# Qwiic_Shield_for_Teensy.net
KiCad netlist of a schematic drawn in EAGLE
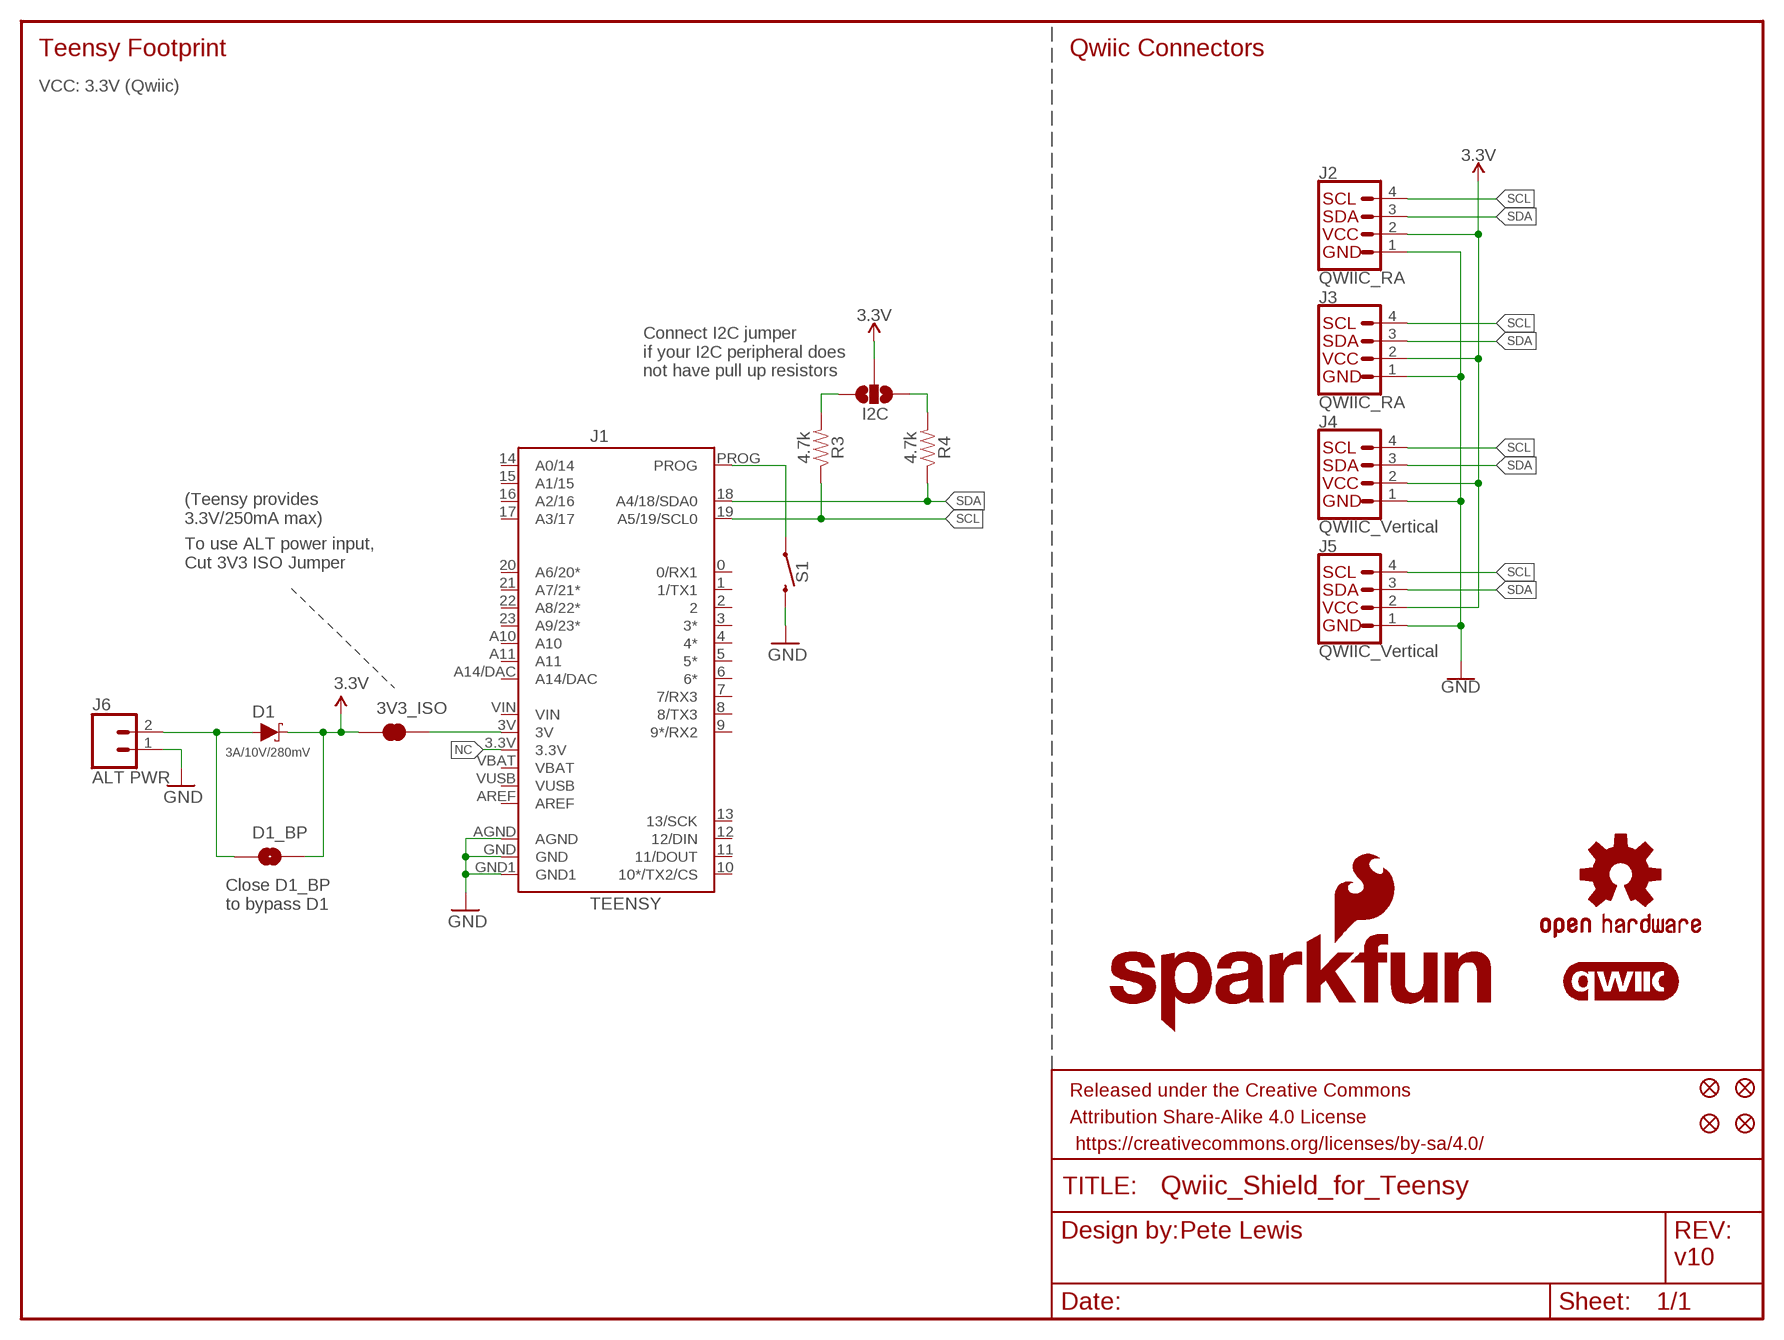
[diagram p0: schematic, sheet 1]

(export (version "E")
  (design (tool "Eeschema 10.0.6"))
  (components
    (comp (ref "3V3_ISO")
      (value "JUMPER-SMT_2_NC_TRACE_SILK")
      (footprint "eagle-import:SMT-JUMPER_2_NC_TRACE_SILK")
      (libsource (lib "eagle-import") (part "JUMPER-SMT_2_NC_TRACE_SILK"))
    )
    (comp (ref "D1")
      (value "3A/10V/280mV")
      (footprint "eagle-import:SOD-323")
      (libsource (lib "eagle-import") (part "DIODE-SCHOTTKY-BAT60A"))
    )
    (comp (ref "D1_BP")
      (value "JUMPER-SMT_2_NO_SILK")
      (footprint "eagle-import:SMT-JUMPER_2_NO_SILK")
      (libsource (lib "eagle-import") (part "JUMPER-SMT_2_NO_SILK"))
    )
    (comp (ref "FD1")
      (value "FIDUCIAL1X2")
      (footprint "eagle-import:FIDUCIAL-1X2")
      (libsource (lib "eagle-import") (part "FIDUCIAL1X2"))
    )
    (comp (ref "FD2")
      (value "FIDUCIAL1X2")
      (footprint "eagle-import:FIDUCIAL-1X2")
      (libsource (lib "eagle-import") (part "FIDUCIAL1X2"))
    )
    (comp (ref "FD3")
      (value "FIDUCIAL1X2")
      (footprint "eagle-import:FIDUCIAL-1X2")
      (libsource (lib "eagle-import") (part "FIDUCIAL1X2"))
    )
    (comp (ref "FD4")
      (value "FIDUCIAL1X2")
      (footprint "eagle-import:FIDUCIAL-1X2")
      (libsource (lib "eagle-import") (part "FIDUCIAL1X2"))
    )
    (comp (ref "FRAME1")
      (value "FRAME-LETTER")
      (footprint "eagle-import:CREATIVE_COMMONS")
      (libsource (lib "eagle-import") (part "FRAME-LETTER"))
    )
    (comp (ref "I2C")
      (value "JUMPER-SMT_3_NO_SILK")
      (footprint "eagle-import:SMT-JUMPER_3_NO_SILK")
      (libsource (lib "eagle-import") (part "JUMPER-SMT_3_NO_SILK"))
    )
    (comp (ref "J1")
      (value "TEENSY")
      (footprint "eagle-import:TEENSY_NOSILK")
      (libsource (lib "eagle-import") (part "TEENSYNOSILK"))
    )
    (comp (ref "J2")
      (value "QWIIC_RA")
      (footprint "eagle-import:JST04_1MM_RA")
      (libsource (lib "eagle-import") (part "QWIIC_CONNECTORJS-1MM"))
    )
    (comp (ref "J3")
      (value "QWIIC_RA")
      (footprint "eagle-import:JST04_1MM_RA")
      (libsource (lib "eagle-import") (part "QWIIC_CONNECTORJS-1MM"))
    )
    (comp (ref "J4")
      (value "QWIIC_Vertical")
      (footprint "eagle-import:JST04_1MM_VERT")
      (libsource (lib "eagle-import") (part "QWIIC_CONNECTOR"))
    )
    (comp (ref "J5")
      (value "QWIIC_Vertical")
      (footprint "eagle-import:JST04_1MM_VERT")
      (libsource (lib "eagle-import") (part "QWIIC_CONNECTOR"))
    )
    (comp (ref "J6")
      (value "ALT PWR")
      (footprint "eagle-import:1X02_NO_SILK")
      (libsource (lib "eagle-import") (part "CONN_021X02_NO_SILK"))
    )
    (comp (ref "LOGO1")
      (value "SFE_LOGO_NAME_FLAME.1_INCH")
      (footprint "eagle-import:SFE_LOGO_NAME_FLAME_.1")
      (libsource (lib "eagle-import") (part "SFE_LOGO_NAME_FLAME.1_INCH"))
    )
    (comp (ref "LOGO2")
      (value "SFE_LOGO_FLAME.1_INCH")
      (footprint "eagle-import:SFE_LOGO_FLAME_.1")
      (libsource (lib "eagle-import") (part "SFE_LOGO_FLAME.1_INCH"))
    )
    (comp (ref "LOGO3")
      (value "OSHW-LOGOS")
      (footprint "eagle-import:OSHW-LOGO-S")
      (libsource (lib "eagle-import") (part "OSHW-LOGOS"))
    )
    (comp (ref "LOGO4")
      (value "QWIIC_LOGO_5MM")
      (footprint "eagle-import:QWIIC_5MM")
      (libsource (lib "eagle-import") (part "QWIIC_LOGO_5MM"))
    )
    (comp (ref "R3")
      (value "4.7k")
      (footprint "eagle-import:0603")
      (libsource (lib "eagle-import") (part "4.7KOHM-0603-1/10W-1%"))
    )
    (comp (ref "R4")
      (value "4.7k")
      (footprint "eagle-import:0603")
      (libsource (lib "eagle-import") (part "4.7KOHM-0603-1/10W-1%"))
    )
    (comp (ref "S1")
      (value "SMD_5.2MM")
      (footprint "eagle-import:TACTILE_SWITCH_SMD_5.2MM")
      (libsource (lib "eagle-import") (part "MOMENTARY-SWITCH-SPST-SMD-5.2MM-TALL"))
    )
  )
  (nets
    (net (code "1") (name "/VBAT") (class "Default")
      (node (ref "J1") (pin "VBAT") (pinfunction "VBAT_VBAT") (pintype "power_in"))
    )
    (net (code "2") (name "/VIN") (class "Default")
      (node (ref "J1") (pin "VIN") (pinfunction "VIN_VIN") (pintype "power_in"))
    )
    (net (code "3") (name "/VUSB") (class "Default")
      (node (ref "J1") (pin "VUSB") (pinfunction "VUSB_VUSB") (pintype "power_in"))
    )
    (net (code "4") (name "3.3V") (class "Default")
      (node (ref "3V3_ISO") (pin "1") (pinfunction "1_1") (pintype "passive"))
      (node (ref "D1") (pin "C") (pinfunction "C_C") (pintype "passive"))
      (node (ref "D1_BP") (pin "2") (pinfunction "2_2") (pintype "passive"))
      (node (ref "I2C") (pin "2") (pinfunction "2_2") (pintype "passive"))
      (node (ref "J2") (pin "2") (pinfunction "2_2") (pintype "power_in"))
      (node (ref "J3") (pin "2") (pinfunction "2_2") (pintype "power_in"))
      (node (ref "J4") (pin "2") (pinfunction "2_2") (pintype "power_in"))
      (node (ref "J5") (pin "2") (pinfunction "2_2") (pintype "power_in"))
    )
    (net (code "5") (name "GND") (class "Default")
      (node (ref "J1") (pin "AGND") (pinfunction "AGND_AGND") (pintype "power_in"))
      (node (ref "J1") (pin "GND") (pinfunction "GND_GND") (pintype "power_in"))
      (node (ref "J1") (pin "GND1") (pinfunction "GND1_GND1") (pintype "power_in"))
      (node (ref "J2") (pin "1") (pinfunction "1_1") (pintype "power_in"))
      (node (ref "J3") (pin "1") (pinfunction "1_1") (pintype "power_in"))
      (node (ref "J4") (pin "1") (pinfunction "1_1") (pintype "power_in"))
      (node (ref "J5") (pin "1") (pinfunction "1_1") (pintype "power_in"))
      (node (ref "J6") (pin "1") (pinfunction "1_1") (pintype "passive"))
      (node (ref "S1") (pin "3") (pinfunction "2_3") (pintype "passive"))
    )
    (net (code "6") (name "NC") (class "Default")
      (node (ref "J1") (pin "3.3V") (pinfunction "3.3V_3.3V") (pintype "power_in"))
    )
    (net (code "7") (name "Net-(3V3_ISO-Pad2)") (class "Default")
      (node (ref "3V3_ISO") (pin "2") (pinfunction "2_2") (pintype "passive"))
      (node (ref "J1") (pin "3V") (pinfunction "3V_3V") (pintype "power_in"))
    )
    (net (code "8") (name "Net-(D1-PadA)") (class "Default")
      (node (ref "D1") (pin "A") (pinfunction "A_A") (pintype "passive"))
      (node (ref "D1_BP") (pin "1") (pinfunction "1_1") (pintype "passive"))
      (node (ref "J6") (pin "2") (pinfunction "2_2") (pintype "passive"))
    )
    (net (code "9") (name "Net-(I2C-Pad1)") (class "Default")
      (node (ref "I2C") (pin "1") (pinfunction "1_1") (pintype "passive"))
      (node (ref "R3") (pin "2") (pinfunction "2_2") (pintype "passive"))
    )
    (net (code "10") (name "Net-(I2C-Pad3)") (class "Default")
      (node (ref "I2C") (pin "3") (pinfunction "3_3") (pintype "passive"))
      (node (ref "R4") (pin "2") (pinfunction "2_2") (pintype "passive"))
    )
    (net (code "11") (name "Net-(J1-PadPROG)") (class "Default")
      (node (ref "J1") (pin "PROG") (pinfunction "PROG_PROG") (pintype "bidirectional"))
      (node (ref "S1") (pin "1") (pinfunction "1_1") (pintype "passive"))
    )
    (net (code "12") (name "SCL") (class "Default")
      (node (ref "J1") (pin "19") (pinfunction "A5/19/SCL0_19") (pintype "bidirectional"))
      (node (ref "J2") (pin "4") (pinfunction "4_4") (pintype "passive"))
      (node (ref "J3") (pin "4") (pinfunction "4_4") (pintype "passive"))
      (node (ref "J4") (pin "4") (pinfunction "4_4") (pintype "passive"))
      (node (ref "J5") (pin "4") (pinfunction "4_4") (pintype "passive"))
      (node (ref "R3") (pin "1") (pinfunction "1_1") (pintype "passive"))
    )
    (net (code "13") (name "SDA") (class "Default")
      (node (ref "J1") (pin "18") (pinfunction "A4/18/SDA0_18") (pintype "bidirectional"))
      (node (ref "J2") (pin "3") (pinfunction "3_3") (pintype "passive"))
      (node (ref "J3") (pin "3") (pinfunction "3_3") (pintype "passive"))
      (node (ref "J4") (pin "3") (pinfunction "3_3") (pintype "passive"))
      (node (ref "J5") (pin "3") (pinfunction "3_3") (pintype "passive"))
      (node (ref "R4") (pin "1") (pinfunction "1_1") (pintype "passive"))
    )
    (net (code "14") (name "unconnected-(J1-0{slash}RX1-Pad0)") (class "Default")
      (node (ref "J1") (pin "0") (pinfunction "0/RX1_0") (pintype "bidirectional"))
    )
    (net (code "15") (name "unconnected-(J1-1{slash}TX1-Pad1)") (class "Default")
      (node (ref "J1") (pin "1") (pinfunction "1/TX1_1") (pintype "bidirectional"))
    )
    (net (code "16") (name "unconnected-(J1-3*-Pad3)") (class "Default")
      (node (ref "J1") (pin "3") (pinfunction "3*_3") (pintype "bidirectional"))
    )
    (net (code "17") (name "unconnected-(J1-4*-Pad4)") (class "Default")
      (node (ref "J1") (pin "4") (pinfunction "4*_4") (pintype "bidirectional"))
    )
    (net (code "18") (name "unconnected-(J1-5*-Pad5)") (class "Default")
      (node (ref "J1") (pin "5") (pinfunction "5*_5") (pintype "bidirectional"))
    )
    (net (code "19") (name "unconnected-(J1-6*-Pad6)") (class "Default")
      (node (ref "J1") (pin "6") (pinfunction "6*_6") (pintype "bidirectional"))
    )
    (net (code "20") (name "unconnected-(J1-7{slash}RX3-Pad7)") (class "Default")
      (node (ref "J1") (pin "7") (pinfunction "7/RX3_7") (pintype "bidirectional"))
    )
    (net (code "21") (name "unconnected-(J1-8{slash}TX3-Pad8)") (class "Default")
      (node (ref "J1") (pin "8") (pinfunction "8/TX3_8") (pintype "bidirectional"))
    )
    (net (code "22") (name "unconnected-(J1-9*{slash}RX2-Pad9)") (class "Default")
      (node (ref "J1") (pin "9") (pinfunction "9*/RX2_9") (pintype "bidirectional"))
    )
    (net (code "23") (name "unconnected-(J1-10*{slash}TX2{slash}CS-Pad10)") (class "Default")
      (node (ref "J1") (pin "10") (pinfunction "10*/TX2/CS_10") (pintype "bidirectional"))
    )
    (net (code "24") (name "unconnected-(J1-11{slash}DOUT-Pad11)") (class "Default")
      (node (ref "J1") (pin "11") (pinfunction "11/DOUT_11") (pintype "bidirectional"))
    )
    (net (code "25") (name "unconnected-(J1-12{slash}DIN-Pad12)") (class "Default")
      (node (ref "J1") (pin "12") (pinfunction "12/DIN_12") (pintype "bidirectional"))
    )
    (net (code "26") (name "unconnected-(J1-13{slash}SCK-Pad13)") (class "Default")
      (node (ref "J1") (pin "13") (pinfunction "13/SCK_13") (pintype "bidirectional"))
    )
    (net (code "27") (name "unconnected-(J1-A0{slash}14-Pad14)") (class "Default")
      (node (ref "J1") (pin "14") (pinfunction "A0/14_14") (pintype "bidirectional"))
    )
    (net (code "28") (name "unconnected-(J1-A1{slash}15-Pad15)") (class "Default")
      (node (ref "J1") (pin "15") (pinfunction "A1/15_15") (pintype "bidirectional"))
    )
    (net (code "29") (name "unconnected-(J1-A2{slash}16-Pad16)") (class "Default")
      (node (ref "J1") (pin "16") (pinfunction "A2/16_16") (pintype "bidirectional"))
    )
    (net (code "30") (name "unconnected-(J1-A3{slash}17-Pad17)") (class "Default")
      (node (ref "J1") (pin "17") (pinfunction "A3/17_17") (pintype "bidirectional"))
    )
    (net (code "31") (name "unconnected-(J1-A6{slash}20*-Pad20)") (class "Default")
      (node (ref "J1") (pin "20") (pinfunction "A6/20*_20") (pintype "bidirectional"))
    )
    (net (code "32") (name "unconnected-(J1-A7{slash}21*-Pad21)") (class "Default")
      (node (ref "J1") (pin "21") (pinfunction "A7/21*_21") (pintype "bidirectional"))
    )
    (net (code "33") (name "unconnected-(J1-A8{slash}22*-Pad22)") (class "Default")
      (node (ref "J1") (pin "22") (pinfunction "A8/22*_22") (pintype "bidirectional"))
    )
    (net (code "34") (name "unconnected-(J1-A9{slash}23*-Pad23)") (class "Default")
      (node (ref "J1") (pin "23") (pinfunction "A9/23*_23") (pintype "bidirectional"))
    )
    (net (code "35") (name "unconnected-(J1-Pad2)") (class "Default")
      (node (ref "J1") (pin "2") (pinfunction "2_2") (pintype "bidirectional"))
    )
    (net (code "36") (name "unconnected-(J1-PadA10)") (class "Default")
      (node (ref "J1") (pin "A10") (pinfunction "A10_A10") (pintype "bidirectional"))
    )
    (net (code "37") (name "unconnected-(J1-PadA11)") (class "Default")
      (node (ref "J1") (pin "A11") (pinfunction "A11_A11") (pintype "bidirectional"))
    )
    (net (code "38") (name "unconnected-(J1-PadA14{slash}DAC)") (class "Default")
      (node (ref "J1") (pin "A14/DAC") (pinfunction "A14/DAC_A14/DAC") (pintype "bidirectional"))
    )
    (net (code "39") (name "unconnected-(J1-PadAREF)") (class "Default")
      (node (ref "J1") (pin "AREF") (pinfunction "AREF_AREF") (pintype "bidirectional"))
    )
  )
)
